# Connectors.net
KiCad netlist of a schematic drawn in Altium Designer
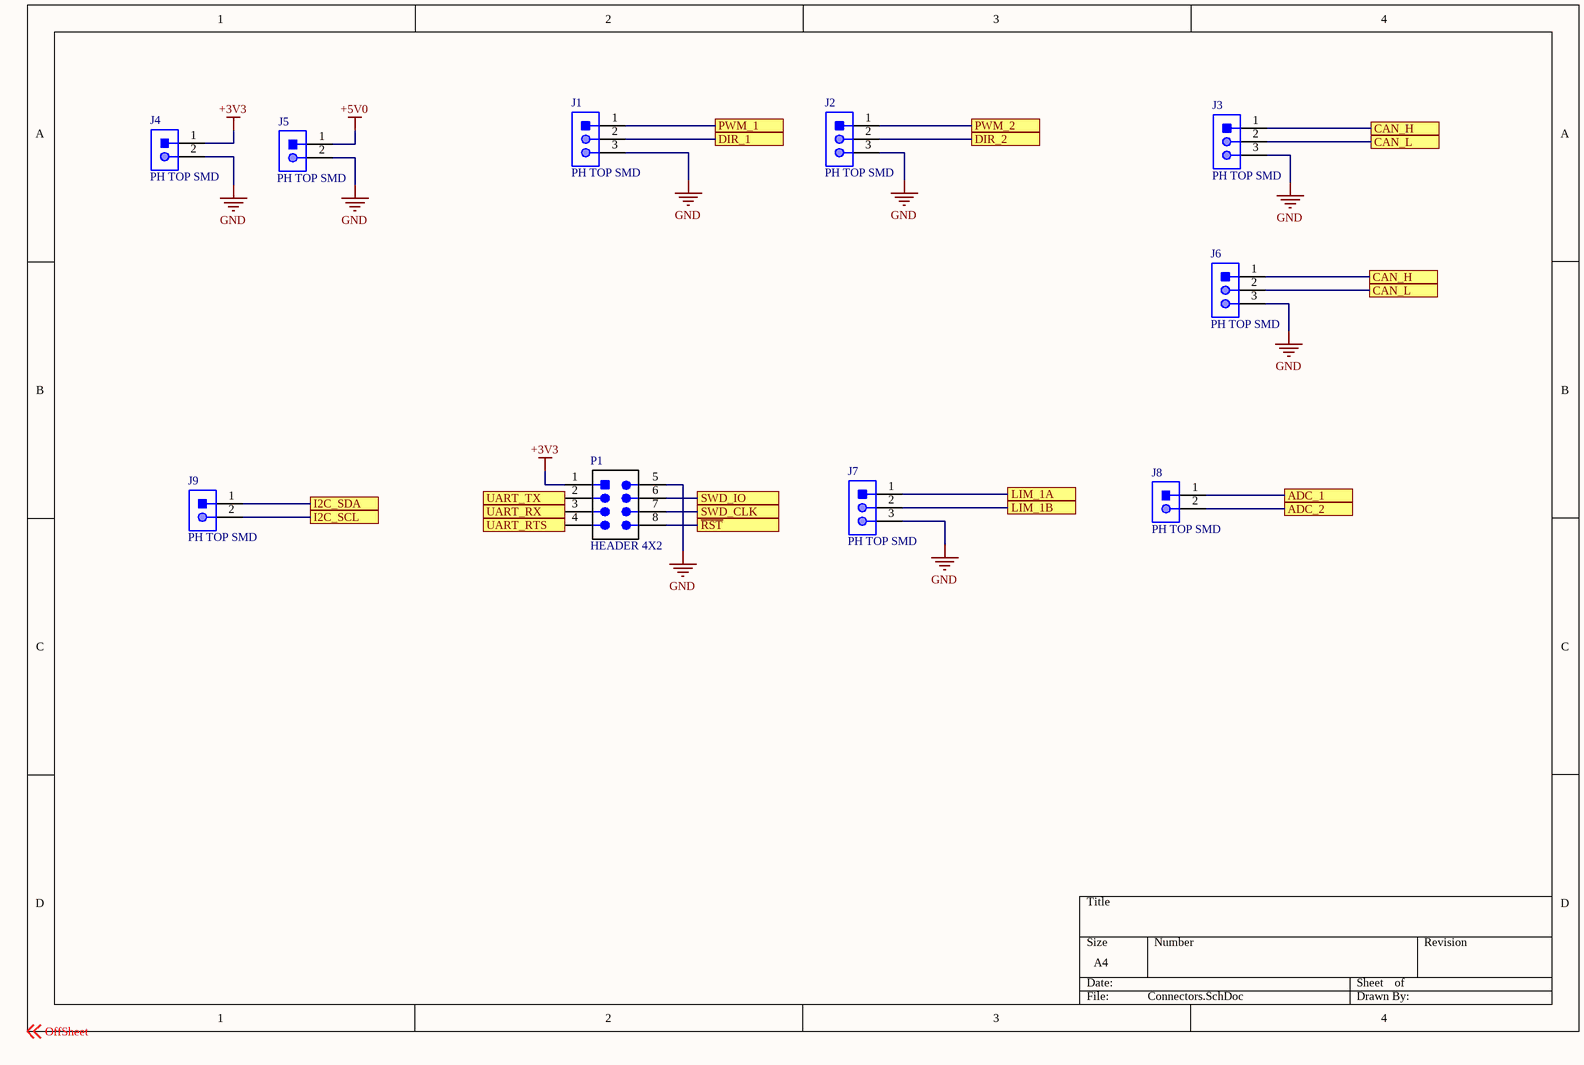
[diagram p0: Connectors.SchDoc]

(export (version "E")
  (design (tool "Eeschema 10.0.6"))
  (components
    (comp (ref "J1")
      (value "PH TOP SMD")
      (footprint "JST-B3B-SM4-TB")
      (description "CONN HEADER PH TOP 3POS 2MM SMD")
      (fields (field (name "MANUFACTURER") "JST") (field (name "PART NUMBER") "B3B-PH-SM4-TB"))
      (libsource (lib "UWRT_Schematic_Library_2019") (part "CON_3M_PH_TOP_SMT"))
    )
    (comp (ref "J2")
      (value "PH TOP SMD")
      (footprint "JST-B3B-SM4-TB")
      (description "CONN HEADER PH TOP 3POS 2MM SMD")
      (fields (field (name "MANUFACTURER") "JST") (field (name "PART NUMBER") "B3B-PH-SM4-TB"))
      (libsource (lib "UWRT_Schematic_Library_2019") (part "CON_3M_PH_TOP_SMT"))
    )
    (comp (ref "J3")
      (value "PH TOP SMD")
      (footprint "JST-B3B-SM4-TB")
      (description "CONN HEADER PH TOP 3POS 2MM SMD")
      (fields (field (name "MANUFACTURER") "JST") (field (name "PART NUMBER") "B3B-PH-SM4-TB"))
      (libsource (lib "UWRT_Schematic_Library_2019") (part "CON_3M_PH_TOP_SMT"))
    )
    (comp (ref "J4")
      (value "PH TOP SMD")
      (footprint "JST-B2B-SM4-TB")
      (description "CONN HEADER PH TOP 2POS 2MM SMD")
      (fields (field (name "MANUFACTURER") "JST") (field (name "PART NUMBER") "B2B-PH-SM4-TB"))
      (libsource (lib "UWRT_Schematic_Library_2019") (part "CON_2M_PH_TOP_SMT"))
    )
    (comp (ref "J5")
      (value "PH TOP SMD")
      (footprint "JST-B2B-SM4-TB")
      (description "CONN HEADER PH TOP 2POS 2MM SMD")
      (fields (field (name "MANUFACTURER") "JST") (field (name "PART NUMBER") "B2B-PH-SM4-TB"))
      (libsource (lib "UWRT_Schematic_Library_2019") (part "CON_2M_PH_TOP_SMT"))
    )
    (comp (ref "J6")
      (value "PH TOP SMD")
      (footprint "JST-B3B-SM4-TB")
      (description "CONN HEADER PH TOP 3POS 2MM SMD")
      (fields (field (name "MANUFACTURER") "JST") (field (name "PART NUMBER") "B3B-PH-SM4-TB"))
      (libsource (lib "UWRT_Schematic_Library_2019") (part "CON_3M_PH_TOP_SMT"))
    )
    (comp (ref "J7")
      (value "PH TOP SMD")
      (footprint "JST-B3B-SM4-TB")
      (description "CONN HEADER PH TOP 3POS 2MM SMD")
      (fields (field (name "MANUFACTURER") "JST") (field (name "PART NUMBER") "B3B-PH-SM4-TB"))
      (libsource (lib "UWRT_Schematic_Library_2019") (part "CON_3M_PH_TOP_SMT"))
    )
    (comp (ref "J8")
      (value "PH TOP SMD")
      (footprint "JST-B2B-SM4-TB")
      (description "CONN HEADER PH TOP 2POS 2MM SMD")
      (fields (field (name "MANUFACTURER") "JST") (field (name "PART NUMBER") "B2B-PH-SM4-TB"))
      (libsource (lib "UWRT_Schematic_Library_2019") (part "CON_2M_PH_TOP_SMT"))
    )
    (comp (ref "J9")
      (value "PH TOP SMD")
      (footprint "JST-B2B-SM4-TB")
      (description "CONN HEADER PH TOP 2POS 2MM SMD")
      (fields (field (name "MANUFACTURER") "JST") (field (name "PART NUMBER") "B2B-PH-SM4-TB"))
      (libsource (lib "UWRT_Schematic_Library_2019") (part "CON_2M_PH_TOP_SMT"))
    )
    (comp (ref "P1")
      (value "HEADER 4X2")
      (footprint "HDR2X4_CEN")
      (description "Header, 4-Pin Dual row")
      (fields (field (name "PUBLISHER") "Altium Limited"))
      (libsource (lib "UWRT_Schematic_Library_2019") (part "HEADER 4X2"))
    )
  )
  (nets
    (net (code "1") (name "+3V3") (class "Default")
      (node (ref "J4") (pin "1") (pinfunction "1_1") (pintype "passive"))
      (node (ref "P1") (pin "1") (pinfunction "VCC_1") (pintype "passive"))
    )
    (net (code "2") (name "+5V0") (class "Default")
      (node (ref "J5") (pin "1") (pinfunction "1_1") (pintype "passive"))
    )
    (net (code "3") (name "/ADC_1") (class "Default")
      (node (ref "J8") (pin "1") (pinfunction "1_1") (pintype "passive"))
    )
    (net (code "4") (name "/ADC_2") (class "Default")
      (node (ref "J8") (pin "2") (pinfunction "2_2") (pintype "passive"))
    )
    (net (code "5") (name "/CAN_H") (class "Default")
      (node (ref "J3") (pin "1") (pinfunction "1_1") (pintype "passive"))
      (node (ref "J6") (pin "1") (pinfunction "1_1") (pintype "passive"))
    )
    (net (code "6") (name "/CAN_L") (class "Default")
      (node (ref "J3") (pin "2") (pinfunction "2_2") (pintype "passive"))
      (node (ref "J6") (pin "2") (pinfunction "2_2") (pintype "passive"))
    )
    (net (code "7") (name "/DIR_1") (class "Default")
      (node (ref "J1") (pin "2") (pinfunction "2_2") (pintype "passive"))
    )
    (net (code "8") (name "/DIR_2") (class "Default")
      (node (ref "J2") (pin "2") (pinfunction "2_2") (pintype "passive"))
    )
    (net (code "9") (name "/I2C_SCL") (class "Default")
      (node (ref "J9") (pin "2") (pinfunction "2_2") (pintype "passive"))
    )
    (net (code "10") (name "/I2C_SDA") (class "Default")
      (node (ref "J9") (pin "1") (pinfunction "1_1") (pintype "passive"))
    )
    (net (code "11") (name "/LIM_1A") (class "Default")
      (node (ref "J7") (pin "1") (pinfunction "1_1") (pintype "passive"))
    )
    (net (code "12") (name "/LIM_1B") (class "Default")
      (node (ref "J7") (pin "2") (pinfunction "2_2") (pintype "passive"))
    )
    (net (code "13") (name "/PWM_1") (class "Default")
      (node (ref "J1") (pin "1") (pinfunction "1_1") (pintype "passive"))
    )
    (net (code "14") (name "/PWM_2") (class "Default")
      (node (ref "J2") (pin "1") (pinfunction "1_1") (pintype "passive"))
    )
    (net (code "15") (name "/SWD_CLK") (class "Default")
      (node (ref "P1") (pin "7") (pinfunction "3_7") (pintype "passive"))
    )
    (net (code "16") (name "/SWD_IO") (class "Default")
      (node (ref "P1") (pin "6") (pinfunction "2_6") (pintype "passive"))
    )
    (net (code "17") (name "/UART_RTS") (class "Default")
      (node (ref "P1") (pin "4") (pinfunction "4_4") (pintype "passive"))
    )
    (net (code "18") (name "/UART_RX") (class "Default")
      (node (ref "P1") (pin "3") (pinfunction "3_3") (pintype "passive"))
    )
    (net (code "19") (name "/UART_TX") (class "Default")
      (node (ref "P1") (pin "2") (pinfunction "2_2") (pintype "passive"))
    )
    (net (code "20") (name "/~{RST}") (class "Default")
      (node (ref "P1") (pin "8") (pinfunction "4_8") (pintype "passive"))
    )
    (net (code "21") (name "GND") (class "Default")
      (node (ref "J1") (pin "3") (pinfunction "3_3") (pintype "passive"))
      (node (ref "J2") (pin "3") (pinfunction "3_3") (pintype "passive"))
      (node (ref "J3") (pin "3") (pinfunction "3_3") (pintype "passive"))
      (node (ref "J4") (pin "2") (pinfunction "2_2") (pintype "passive"))
      (node (ref "J5") (pin "2") (pinfunction "2_2") (pintype "passive"))
      (node (ref "J6") (pin "3") (pinfunction "3_3") (pintype "passive"))
      (node (ref "J7") (pin "3") (pinfunction "3_3") (pintype "passive"))
      (node (ref "P1") (pin "5") (pinfunction "GND_5") (pintype "passive"))
    )
  )
)
